# gnss_gps.net
KiCad netlist of a schematic drawn in Altium Designer
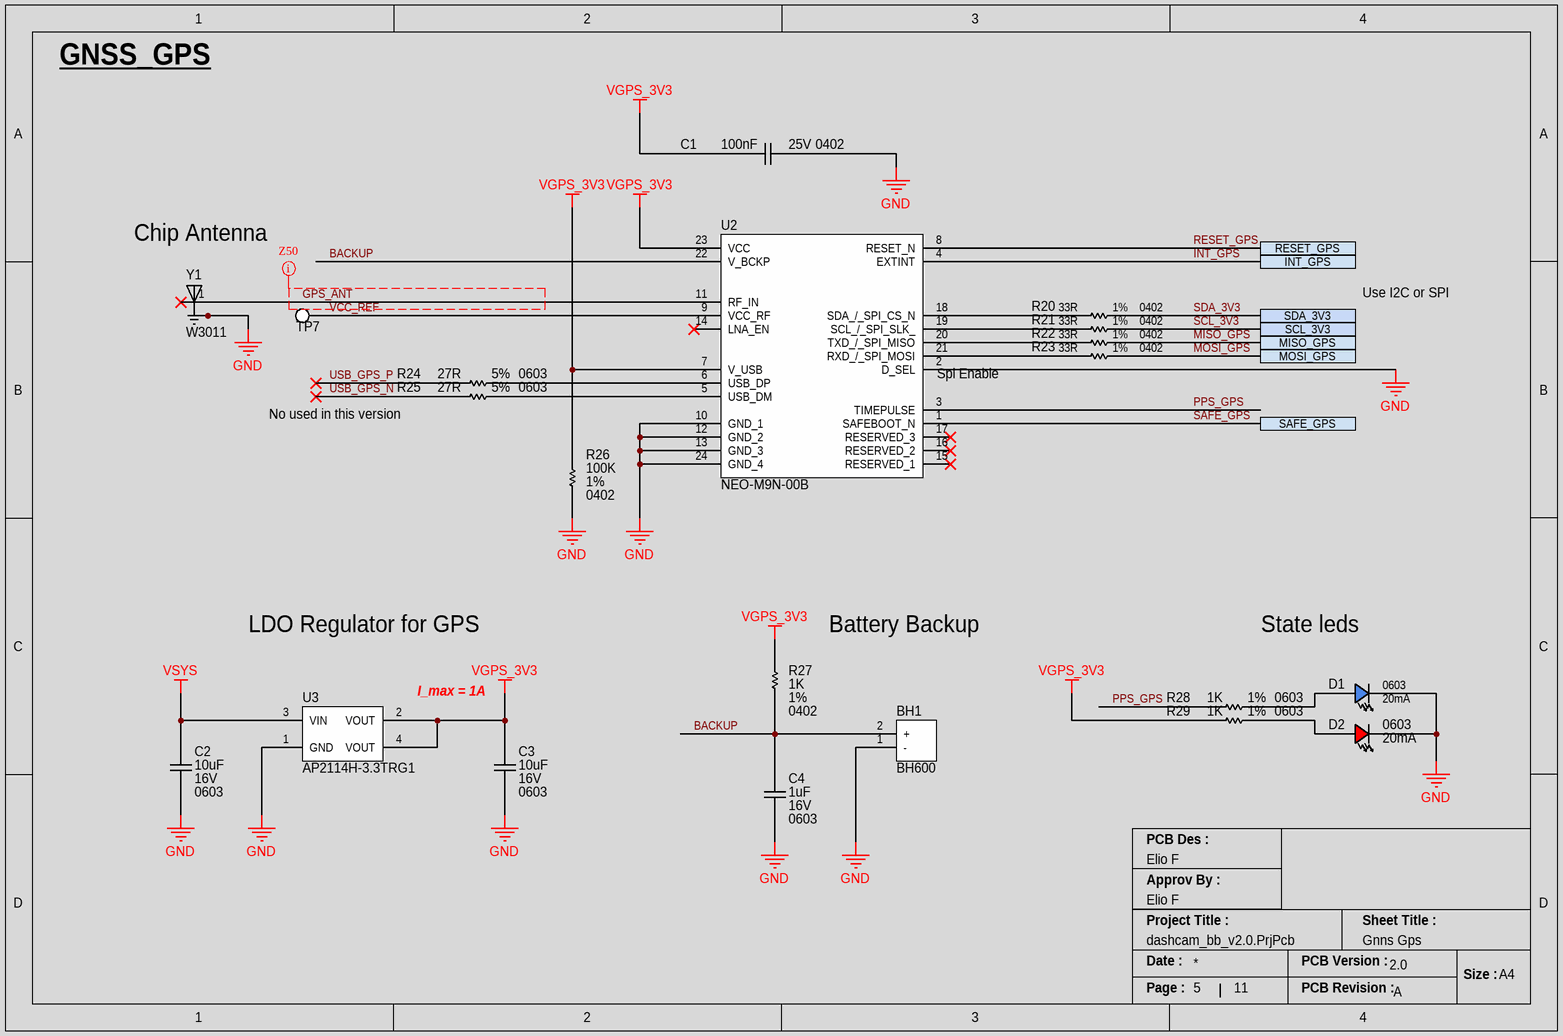
[diagram p0: gnss_gps.SchDoc]

(export (version "E")
  (design (tool "Eeschema 10.0.6"))
  (components
    (comp (ref "BH1")
      (value "BH600")
      (footprint "MECH_BATTERY_HOLDER_BH600")
      (description "Battery Holder 1 Cells Thermoplastic Tray")
      (fields (field (name "MANUFACTURER") "Memory Protection Devices"))
      (libsource (lib "Electronic Devices_LIB") (part "MECH_BATTERY_HOLDER_BH600"))
    )
    (comp (ref "C1")
      (value "CC0402KRX5R8BB104")
      (footprint "CAP_0402_CAPC1005X05N")
      (description "Multilayer Ceramic Capacitor, 0.1 uF, 25 V, ± 10%, X7R, 0402 [1005 Metric]")
      (fields
        (field (name "MANUFACTURER") "Yageo")
        (field (name "TOLERANCE") "10%")
        (field (name "CAPACITANCE") "100nF")
        (field (name "VOLTAGE RATING") "25V")
        (field (name "CASE/PACKAGE") "0402")
      )
      (libsource (lib "Electronic Devices_LIB") (part "CAP_100NF_25V_X7R_0402"))
    )
    (comp (ref "C2")
      (value "GRM188R61C106MAALD")
      (footprint "CAP_0603_CAPC1608X08N")
      (description "0603 10 uF 16 V ±20% Tolerance X5R Multilayer Ceramic Chip Capacitor")
      (fields
        (field (name "MANUFACTURER") "Murata")
        (field (name "TOLERANCE") "20%")
        (field (name "VOLTAGE RATING") "16V")
        (field (name "CAPACITANCE") "10uF")
        (field (name "CASE/PACKAGE") "0603")
      )
      (libsource (lib "Electronic Devices_LIB") (part "CAP_10UF_16V_X5R_0603"))
    )
    (comp (ref "C3")
      (value "GRM188R61C106MAALD")
      (footprint "CAP_0603_CAPC1608X08N")
      (description "0603 10 uF 16 V ±20% Tolerance X5R Multilayer Ceramic Chip Capacitor")
      (fields
        (field (name "MANUFACTURER") "Murata")
        (field (name "TOLERANCE") "20%")
        (field (name "VOLTAGE RATING") "16V")
        (field (name "CAPACITANCE") "10uF")
        (field (name "CASE/PACKAGE") "0603")
      )
      (libsource (lib "Electronic Devices_LIB") (part "CAP_10UF_16V_X5R_0603"))
    )
    (comp (ref "C4")
      (value "CL10A105KO8NNNC")
      (footprint "CAP_0603_CAPC1608X08N")
      (description "CAP CER 1UF 16V X5R 0603")
      (fields
        (field (name "MANUFACTURER") "Samsung")
        (field (name "TOLERANCE") "10%")
        (field (name "VOLTAGE RATING") "16V")
        (field (name "CAPACITANCE") "1uF")
        (field (name "CASE/PACKAGE") "0603")
      )
      (libsource (lib "Electronic Devices_LIB") (part "CAP_1UF_16V_X5R_0603"))
    )
    (comp (ref "D1")
      (value "ASCKCB00-NS3T4010302")
      (footprint "LED_0603-BLUE-0.75mm")
      (description "LED Single Chip Blue 467nm 20mA 2-Pin DFN T/R")
      (fields
        (field (name "MANUFACTURER") "Broadcom")
        (field (name "CASE/PACKCAGE") "0603")
        (field (name "TEST CURRENT") "20mA")
      )
      (libsource (lib "Electronic Devices_LIB") (part "LED_DIO_BLUE_20mA_0603_ASCKCB00-NS3T4010302"))
    )
    (comp (ref "D2")
      (value "LTST-C190KRKT")
      (footprint "LED_0603-RED-0.75mm")
      (description "LED,  LTST-C190KRKT")
      (fields
        (field (name "MANUFACTURER") "Vishay Lite-On")
        (field (name "TEST CURRENT") "20mA")
        (field (name "CASE/PACKAGE") "0603")
      )
      (libsource (lib "Electronic Devices_LIB") (part "LED_DIO_RED_20mA_0603"))
    )
    (comp (ref "R20")
      (value "RC0402FR-0733RL")
      (footprint "RES_0402_RESC1005X04N")
      (description "SMD Chip Resistor, 33 Ohm, ± 1%, 62.5 mW, 0402 [1005 Metric], Thick Film, General Purpose")
      (fields
        (field (name "MANUFACTURER") "Yageo")
        (field (name "TOLERANCE") "1%")
        (field (name "RESISTANCE") "33R")
        (field (name "CASE/PACKAGE") "0402")
      )
      (libsource (lib "Electronic Devices_LIB") (part "RES_33R_1%_62.5mW_0402"))
    )
    (comp (ref "R21")
      (value "RC0402FR-0733RL")
      (footprint "RES_0402_RESC1005X04N")
      (description "SMD Chip Resistor, 33 Ohm, ± 1%, 62.5 mW, 0402 [1005 Metric], Thick Film, General Purpose")
      (fields
        (field (name "MANUFACTURER") "Yageo")
        (field (name "TOLERANCE") "1%")
        (field (name "RESISTANCE") "33R")
        (field (name "CASE/PACKAGE") "0402")
      )
      (libsource (lib "Electronic Devices_LIB") (part "RES_33R_1%_62.5mW_0402"))
    )
    (comp (ref "R22")
      (value "RC0402FR-0733RL")
      (footprint "RES_0402_RESC1005X04N")
      (description "SMD Chip Resistor, 33 Ohm, ± 1%, 62.5 mW, 0402 [1005 Metric], Thick Film, General Purpose")
      (fields
        (field (name "MANUFACTURER") "Yageo")
        (field (name "TOLERANCE") "1%")
        (field (name "RESISTANCE") "33R")
        (field (name "CASE/PACKAGE") "0402")
      )
      (libsource (lib "Electronic Devices_LIB") (part "RES_33R_1%_62.5mW_0402"))
    )
    (comp (ref "R23")
      (value "RC0402FR-0733RL")
      (footprint "RES_0402_RESC1005X04N")
      (description "SMD Chip Resistor, 33 Ohm, ± 1%, 62.5 mW, 0402 [1005 Metric], Thick Film, General Purpose")
      (fields
        (field (name "MANUFACTURER") "Yageo")
        (field (name "TOLERANCE") "1%")
        (field (name "RESISTANCE") "33R")
        (field (name "CASE/PACKAGE") "0402")
      )
      (libsource (lib "Electronic Devices_LIB") (part "RES_33R_1%_62.5mW_0402"))
    )
    (comp (ref "R24")
      (value "RC0603JR-0727RL")
      (footprint "RES_0603_RESC1608X04N")
      (description "Res Thick Film 0603 27 Ohm 5% 0.1W(1/10W) ±100ppm/C Pad SMD T/R")
      (fields
        (field (name "MANUFACTURER") "Yageo")
        (field (name "TOLERANCE") "5%")
        (field (name "RESISTANCE") "27R")
        (field (name "CASE/PACKAGE") "0603")
      )
      (libsource (lib "Electronic Devices_LIB") (part "RES_27R_5%_100mW_0603"))
    )
    (comp (ref "R25")
      (value "RC0603JR-0727RL")
      (footprint "RES_0603_RESC1608X04N")
      (description "Res Thick Film 0603 27 Ohm 5% 0.1W(1/10W) ±100ppm/C Pad SMD T/R")
      (fields
        (field (name "MANUFACTURER") "Yageo")
        (field (name "TOLERANCE") "5%")
        (field (name "RESISTANCE") "27R")
        (field (name "CASE/PACKAGE") "0603")
      )
      (libsource (lib "Electronic Devices_LIB") (part "RES_27R_5%_100mW_0603"))
    )
    (comp (ref "R26")
      (value "RC0402FR-07100KL")
      (footprint "RES_0402_RESC1005X04N")
      (description "SMD Chip Resistor, 100 kOhm, ± 1%, 63 mW, 0402 [1005 Metric], Thick Film, General Purpose")
      (fields
        (field (name "MANUFACTURER") "Yageo")
        (field (name "RESISTANCE") "100K")
        (field (name "TOLERANCE") "1%")
        (field (name "CASE/PACKAGE") "0402")
      )
      (libsource (lib "Electronic Devices_LIB") (part "RES_100K_1%_100mW_0402"))
    )
    (comp (ref "R27")
      (value "ERJ-2RKF1001X")
      (footprint "RES_0402_RESC1005X04N")
      (description "RES SMD 1K OHM 1% 1/10W 0402")
      (fields
        (field (name "MANUFACTURER") "Panasonic")
        (field (name "RESISTANCE") "1K")
        (field (name "TOLERANCE") "1%")
        (field (name "CASE/PACKAGE") "0402")
      )
      (libsource (lib "Electronic Devices_LIB") (part "RES_1K_1%_100mW_0402"))
    )
    (comp (ref "R28")
      (value "AC0603FR-101KL")
      (footprint "RES_0603_RESC1608X04N")
      (description "Chip Resistor Automotive Grade Thick Film 0603 1kOhm 1% Paper T/R")
      (fields
        (field (name "MANUFACTURER") "Yageo")
        (field (name "RESISTANCE") "1K")
        (field (name "TOLERANCE") "1%")
        (field (name "CASE/PACKAGE") "0603")
      )
      (libsource (lib "Electronic Devices_LIB") (part "RES_1K_1%_100mW_0603"))
    )
    (comp (ref "R29")
      (value "AC0603FR-101KL")
      (footprint "RES_0603_RESC1608X04N")
      (description "Chip Resistor Automotive Grade Thick Film 0603 1kOhm 1% Paper T/R")
      (fields
        (field (name "MANUFACTURER") "Yageo")
        (field (name "RESISTANCE") "1K")
        (field (name "TOLERANCE") "1%")
        (field (name "CASE/PACKAGE") "0603")
      )
      (libsource (lib "Electronic Devices_LIB") (part "RES_1K_1%_100mW_0603"))
    )
    (comp (ref "TP7")
      (value "NO COMPONENT")
      (footprint "TP_PAD_1.6MM_SMD_ROUND")
      (description "Test Point, SMD pad, round, 1.5mm, 1.6mm, 3mm diameter")
      (libsource (lib "Electronic Devices_LIB") (part "TP_PAD_SMD_Round"))
    )
    (comp (ref "U2")
      (value "NEO-M9N-00B")
      (footprint "IC_MODULE_UBLOX_NEOM9N00B")
      (description "GNSS module, Flash, TCXO, SAW, LNA, LCC, 12x16 mm Professional Grade")
      (fields (field (name "MANUFACTURER") "u-blox"))
      (libsource (lib "Electronic Devices_LIB") (part "IC_MODULE_UBLOX_NEO-M9N-00B"))
    )
    (comp (ref "U3")
      (value "AP2114H-3.3TRG1")
      (footprint "IC_REG_SOT230P700X180-4N")
      (description "IC REG LDO 3.3V 1A SOT223")
      (fields (field (name "MANUFACTURER") "Diodes"))
      (libsource (lib "Electronic Devices_LIB") (part "IC_REG_LDO_3.3V_1A_AP2114H-3.3TRG1"))
    )
    (comp (ref "Y1")
      (value "W3011")
      (footprint "ANTENNA_CHIP_XDCR_W3011")
      (description "Antenna Ceramic 3.4dB Gain 1585.42MHz 2-Pin CSMD")
      (fields (field (name "MANUFACTURER") "Pulse"))
      (libsource (lib "Electronic Devices_LIB") (part "ANT_CHIP_GPS_W3011"))
    )
  )
  (nets
    (net (code "1") (name "/BACKUP") (class "Default")
      (node (ref "BH1") (pin "2") (pinfunction "+_2") (pintype "passive"))
      (node (ref "C4") (pin "2") (pinfunction "2_2") (pintype "passive"))
      (node (ref "R27") (pin "1") (pinfunction "1_1") (pintype "passive"))
      (node (ref "U2") (pin "22") (pinfunction "V_BCKP_22") (pintype "passive"))
    )
    (net (code "2") (name "/GPS_ANT") (class "Default")
      (node (ref "U2") (pin "11") (pinfunction "RF_IN_11") (pintype "passive"))
      (node (ref "Y1") (pin "1") (pinfunction "FEED_1") (pintype "passive"))
    )
    (net (code "3") (name "/INT_GPS") (class "Default")
      (node (ref "U2") (pin "4") (pinfunction "EXTINT_4") (pintype "passive"))
    )
    (net (code "4") (name "/MISO_GPS") (class "Default")
      (node (ref "R22") (pin "2") (pinfunction "2_2") (pintype "passive"))
    )
    (net (code "5") (name "/MOSI_GPS") (class "Default")
      (node (ref "R23") (pin "2") (pinfunction "2_2") (pintype "passive"))
    )
    (net (code "6") (name "/PPS_GPS") (class "Default")
      (node (ref "R28") (pin "1") (pinfunction "1_1") (pintype "passive"))
      (node (ref "U2") (pin "3") (pinfunction "TIMEPULSE_3") (pintype "passive"))
    )
    (net (code "7") (name "/RESET_GPS") (class "Default")
      (node (ref "U2") (pin "8") (pinfunction "RESET_N_8") (pintype "passive"))
    )
    (net (code "8") (name "/SAFE_GPS") (class "Default")
      (node (ref "U2") (pin "1") (pinfunction "SAFEBOOT_N_1") (pintype "passive"))
    )
    (net (code "9") (name "/SCL_3V3") (class "Default")
      (node (ref "R21") (pin "2") (pinfunction "2_2") (pintype "passive"))
    )
    (net (code "10") (name "/SDA_3V3") (class "Default")
      (node (ref "R20") (pin "2") (pinfunction "2_2") (pintype "passive"))
    )
    (net (code "11") (name "/USB_GPS_N") (class "Default")
      (node (ref "R25") (pin "1") (pinfunction "1_1") (pintype "passive+no_connect"))
    )
    (net (code "12") (name "/USB_GPS_P") (class "Default")
      (node (ref "R24") (pin "1") (pinfunction "1_1") (pintype "passive+no_connect"))
    )
    (net (code "13") (name "/VCC_REF") (class "Default")
      (node (ref "TP7") (pin "1") (pinfunction "1_1") (pintype "passive"))
      (node (ref "U2") (pin "9") (pinfunction "VCC_RF_9") (pintype "passive"))
    )
    (net (code "14") (name "GND") (class "Default")
      (node (ref "BH1") (pin "1") (pinfunction "-_1") (pintype "passive"))
      (node (ref "C1") (pin "2") (pinfunction "2_2") (pintype "passive"))
      (node (ref "C2") (pin "1") (pinfunction "1_1") (pintype "passive"))
      (node (ref "C3") (pin "1") (pinfunction "1_1") (pintype "passive"))
      (node (ref "C4") (pin "1") (pinfunction "1_1") (pintype "passive"))
      (node (ref "D1") (pin "1") (pinfunction "C_1") (pintype "passive"))
      (node (ref "D2") (pin "1") (pinfunction "C_1") (pintype "passive"))
      (node (ref "R26") (pin "1") (pinfunction "1_1") (pintype "passive"))
      (node (ref "U2") (pin "10") (pinfunction "GND_1_10") (pintype "passive"))
      (node (ref "U2") (pin "12") (pinfunction "GND_2_12") (pintype "passive"))
      (node (ref "U2") (pin "13") (pinfunction "GND_3_13") (pintype "passive"))
      (node (ref "U2") (pin "2") (pinfunction "D_SEL_2") (pintype "passive"))
      (node (ref "U2") (pin "24") (pinfunction "GND_4_24") (pintype "passive"))
      (node (ref "U3") (pin "1") (pinfunction "GND_1") (pintype "passive"))
      (node (ref "Y1") (pin "2") (pinfunction "GND_2") (pintype "power_in"))
      (node (ref "Y1") (pin "3") (pinfunction "GND_3") (pintype "passive"))
    )
    (net (code "15") (name "Net-(D1-A)") (class "Default")
      (node (ref "D1") (pin "2") (pinfunction "A_2") (pintype "passive"))
      (node (ref "R28") (pin "2") (pinfunction "2_2") (pintype "passive"))
    )
    (net (code "16") (name "Net-(D2-A)") (class "Default")
      (node (ref "D2") (pin "2") (pinfunction "A_2") (pintype "passive"))
      (node (ref "R29") (pin "2") (pinfunction "2_2") (pintype "passive"))
    )
    (net (code "17") (name "Net-(U2-RXD_{slash}_SPI_MOSI)") (class "Default")
      (node (ref "R23") (pin "1") (pinfunction "1_1") (pintype "passive"))
      (node (ref "U2") (pin "21") (pinfunction "RXD_/_SPI_MOSI_21") (pintype "passive"))
    )
    (net (code "18") (name "Net-(U2-SCL_{slash}_SPI_SLK_)") (class "Default")
      (node (ref "R21") (pin "1") (pinfunction "1_1") (pintype "passive"))
      (node (ref "U2") (pin "19") (pinfunction "SCL_/_SPI_SLK__19") (pintype "passive"))
    )
    (net (code "19") (name "Net-(U2-SDA_{slash}_SPI_CS_N)") (class "Default")
      (node (ref "R20") (pin "1") (pinfunction "1_1") (pintype "passive"))
      (node (ref "U2") (pin "18") (pinfunction "SDA_/_SPI_CS_N_18") (pintype "passive"))
    )
    (net (code "20") (name "Net-(U2-TXD_{slash}_SPI_MISO)") (class "Default")
      (node (ref "R22") (pin "1") (pinfunction "1_1") (pintype "passive"))
      (node (ref "U2") (pin "20") (pinfunction "TXD_/_SPI_MISO_20") (pintype "passive"))
    )
    (net (code "21") (name "Net-(U2-USB_DM)") (class "Default")
      (node (ref "R25") (pin "2") (pinfunction "2_2") (pintype "passive"))
      (node (ref "U2") (pin "5") (pinfunction "USB_DM_5") (pintype "passive"))
    )
    (net (code "22") (name "Net-(U2-USB_DP)") (class "Default")
      (node (ref "R24") (pin "2") (pinfunction "2_2") (pintype "passive"))
      (node (ref "U2") (pin "6") (pinfunction "USB_DP_6") (pintype "passive"))
    )
    (net (code "23") (name "VGPS_3V3") (class "Default")
      (node (ref "C1") (pin "1") (pinfunction "1_1") (pintype "passive"))
      (node (ref "C3") (pin "2") (pinfunction "2_2") (pintype "passive"))
      (node (ref "R26") (pin "2") (pinfunction "2_2") (pintype "passive"))
      (node (ref "R27") (pin "2") (pinfunction "2_2") (pintype "passive"))
      (node (ref "R29") (pin "1") (pinfunction "1_1") (pintype "passive"))
      (node (ref "U2") (pin "23") (pinfunction "VCC_23") (pintype "passive"))
      (node (ref "U2") (pin "7") (pinfunction "V_USB_7") (pintype "passive"))
      (node (ref "U3") (pin "2") (pinfunction "VOUT_2") (pintype "passive"))
      (node (ref "U3") (pin "4") (pinfunction "VOUT_4") (pintype "passive"))
    )
    (net (code "24") (name "VSYS") (class "Default")
      (node (ref "C2") (pin "2") (pinfunction "2_2") (pintype "passive"))
      (node (ref "U3") (pin "3") (pinfunction "VIN_3") (pintype "passive"))
    )
    (net (code "25") (name "unconnected-(U2-LNA_EN-Pad14)") (class "Default")
      (node (ref "U2") (pin "14") (pinfunction "LNA_EN_14") (pintype "passive+no_connect"))
    )
    (net (code "26") (name "unconnected-(U2-RESERVED_1-Pad15)") (class "Default")
      (node (ref "U2") (pin "15") (pinfunction "RESERVED_1_15") (pintype "passive+no_connect"))
    )
    (net (code "27") (name "unconnected-(U2-RESERVED_2-Pad16)") (class "Default")
      (node (ref "U2") (pin "16") (pinfunction "RESERVED_2_16") (pintype "passive+no_connect"))
    )
    (net (code "28") (name "unconnected-(U2-RESERVED_3-Pad17)") (class "Default")
      (node (ref "U2") (pin "17") (pinfunction "RESERVED_3_17") (pintype "passive+no_connect"))
    )
    (net (code "29") (name "unconnected-(Y1-NC-Pad2)") (class "Default")
      (node (ref "Y1") (pin "2") (pinfunction "NC_2") (pintype "passive+no_connect"))
    )
  )
)
